# HF1R00.net
KiCad netlist of a schematic drawn in EAGLE
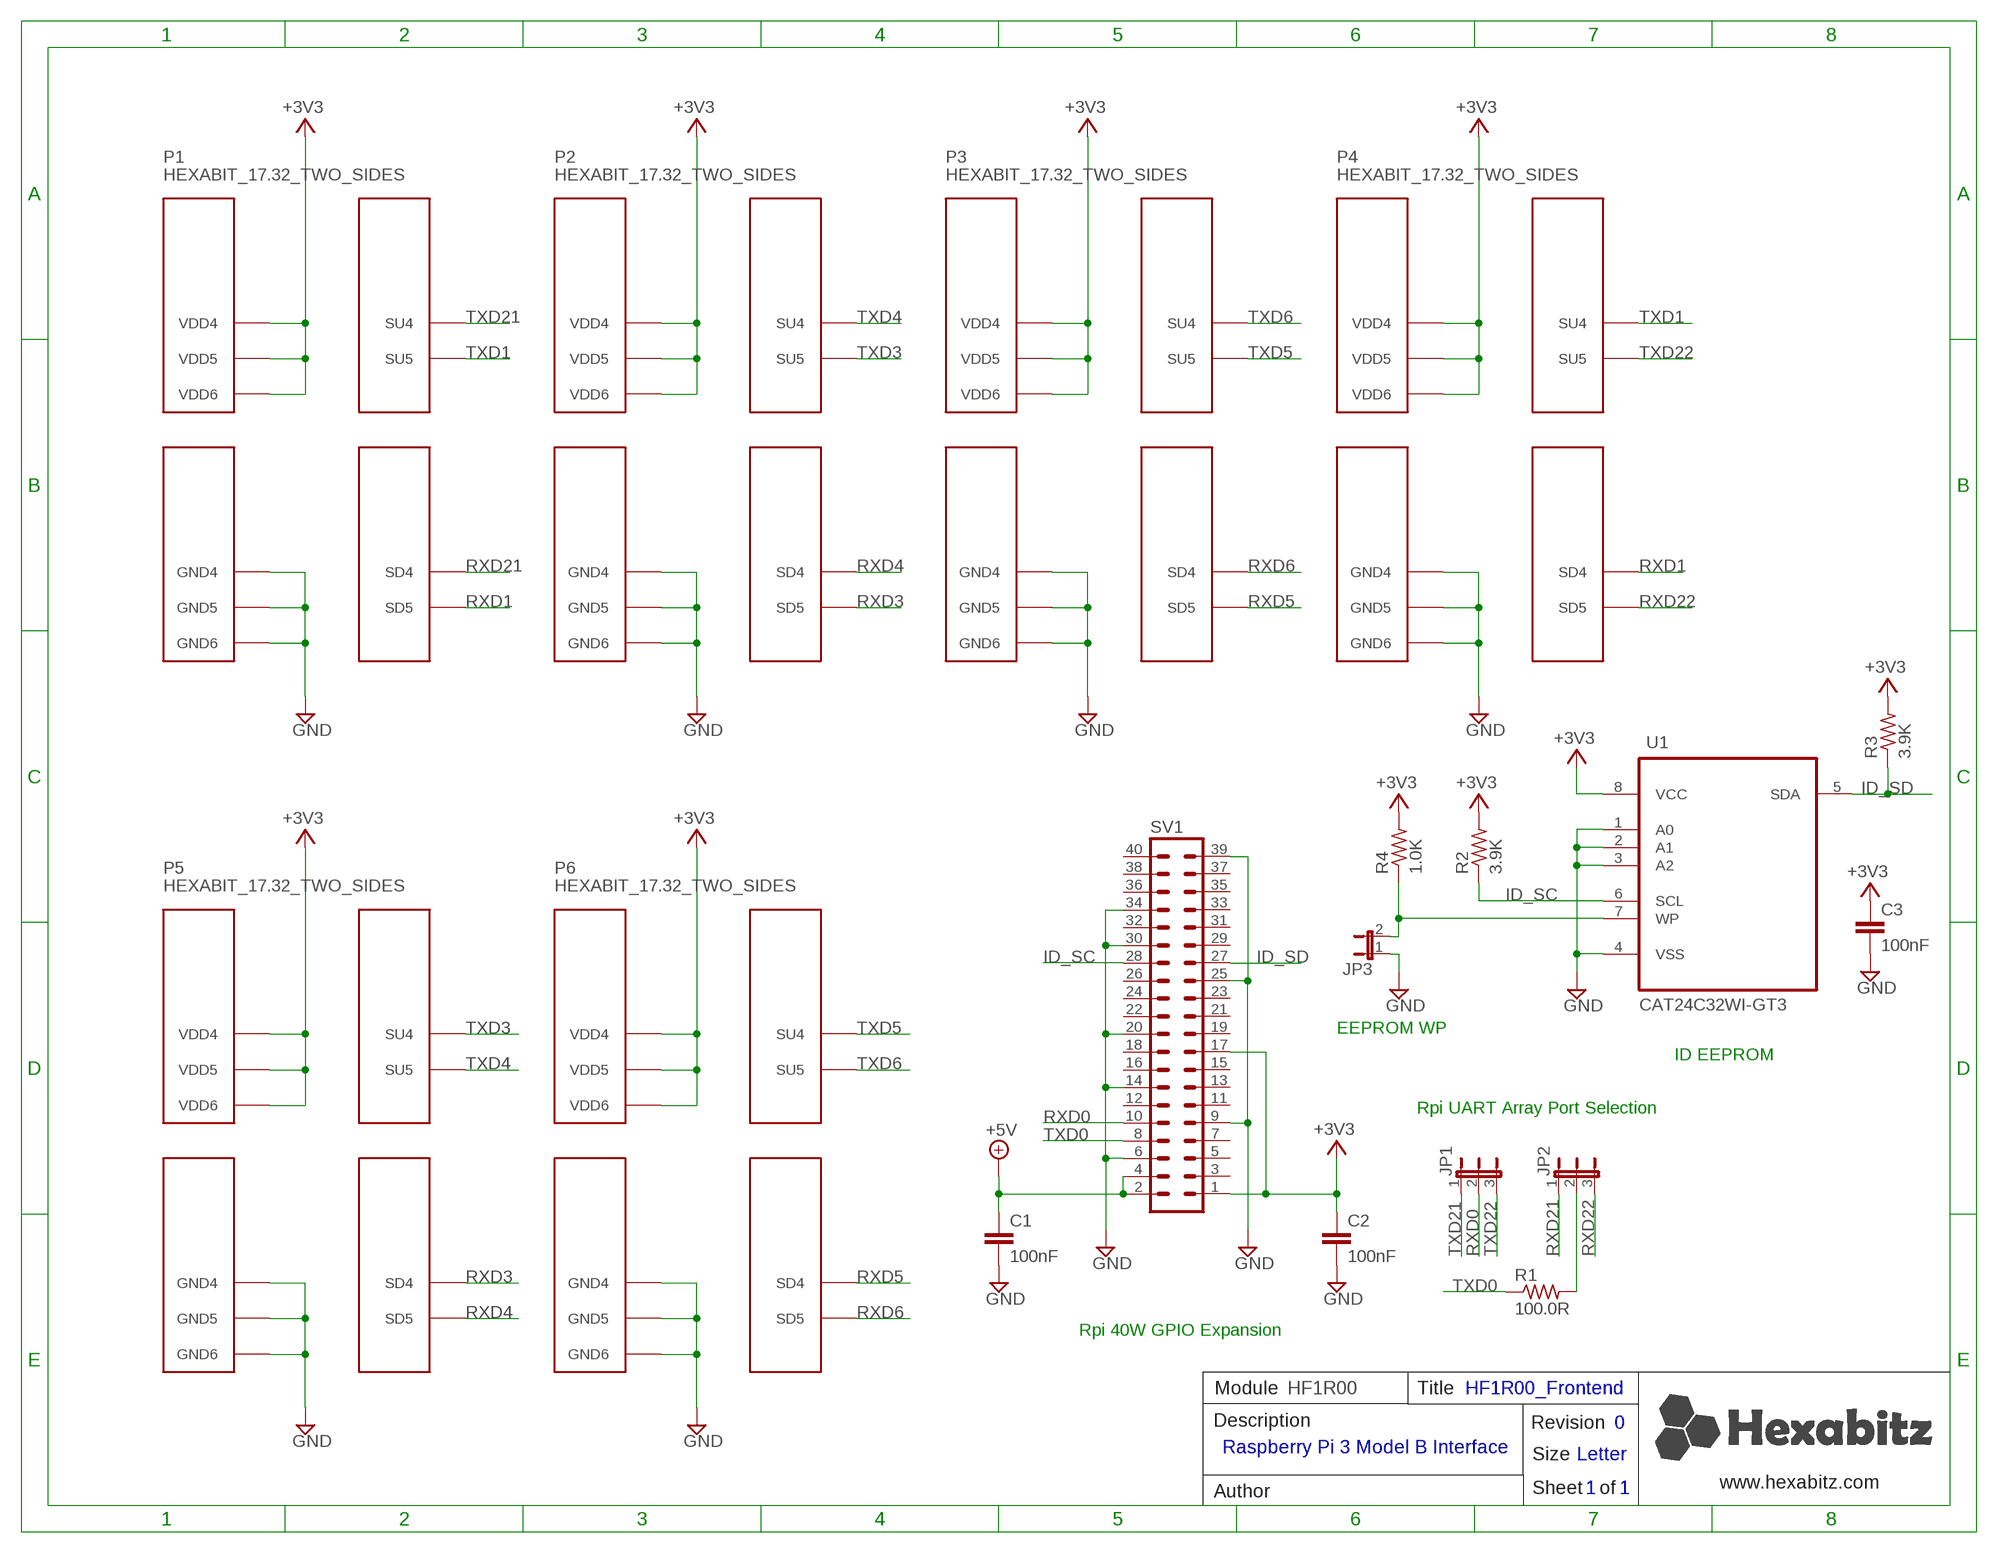
[diagram p0: schematic, sheet 1]

(export (version "E")
  (design (tool "Eeschema 10.0.6"))
  (components
    (comp (ref "C1")
      (value "100nF")
      (footprint "eagle-import:C-0603")
      (fields
        (field (name "CAPACITANCE") "100nF")
        (field (name "MFN") "KEMET")
        (field (name "MPN") "C0603C104K8RACTU")
        (field (name "OCTOPART_URL") "https://octopart.com/c0603c104k8ractu-kemet-145075?r=sp&s=9bS9ASSwSEqMCE9KBEQZ0g")
        (field (name "TOLERANCE") "10V")
        (field (name "VOLTAGE_RATING") "10%")
      )
      (libsource (lib "eagle-import") (part "C-0603"))
    )
    (comp (ref "C2")
      (value "100nF")
      (footprint "eagle-import:C-0603")
      (fields
        (field (name "CAPACITANCE") "100nF")
        (field (name "MFN") "KEMET")
        (field (name "MPN") "C0603C104K8RACTU")
        (field (name "OCTOPART_URL") "https://octopart.com/c0603c104k8ractu-kemet-145075?r=sp&s=9bS9ASSwSEqMCE9KBEQZ0g")
        (field (name "TOLERANCE") "10V")
        (field (name "VOLTAGE_RATING") "10%")
      )
      (libsource (lib "eagle-import") (part "C-0603"))
    )
    (comp (ref "C3")
      (value "100nF")
      (footprint "eagle-import:C-0603")
      (fields
        (field (name "CAPACITANCE") "100nF")
        (field (name "MFN") "KEMET")
        (field (name "MPN") "C0603C104K8RACTU")
        (field (name "OCTOPART_URL") "https://octopart.com/c0603c104k8ractu-kemet-145075?r=sp&s=9bS9ASSwSEqMCE9KBEQZ0g")
        (field (name "TOLERANCE") "10V")
        (field (name "VOLTAGE_RATING") "10%")
      )
      (libsource (lib "eagle-import") (part "C-0603"))
    )
    (comp (ref "JP1")
      (value "61300311121")
      (footprint "eagle-import:JP2")
      (libsource (lib "eagle-import") (part "JP2E"))
    )
    (comp (ref "JP2")
      (value "61300311121")
      (footprint "eagle-import:JP2")
      (libsource (lib "eagle-import") (part "JP2E"))
    )
    (comp (ref "JP3")
      (value "61300211121")
      (footprint "eagle-import:JP1")
      (libsource (lib "eagle-import") (part "JP1E"))
    )
    (comp (ref "P1")
      (value "HEXABIT_17.32_TWO_SIDES")
      (footprint "eagle-import:HEXABIT_17.32_TWO_SIDES")
      (libsource (lib "eagle-import") (part "HEXABIT_?_TWO_SIDES17.32"))
    )
    (comp (ref "P2")
      (value "HEXABIT_17.32_TWO_SIDES")
      (footprint "eagle-import:HEXABIT_17.32_TWO_SIDES")
      (libsource (lib "eagle-import") (part "HEXABIT_?_TWO_SIDES17.32"))
    )
    (comp (ref "P3")
      (value "HEXABIT_17.32_TWO_SIDES")
      (footprint "eagle-import:HEXABIT_17.32_TWO_SIDES")
      (libsource (lib "eagle-import") (part "HEXABIT_?_TWO_SIDES17.32"))
    )
    (comp (ref "P4")
      (value "HEXABIT_17.32_TWO_SIDES")
      (footprint "eagle-import:HEXABIT_17.32_TWO_SIDES")
      (libsource (lib "eagle-import") (part "HEXABIT_?_TWO_SIDES17.32"))
    )
    (comp (ref "P5")
      (value "HEXABIT_17.32_TWO_SIDES")
      (footprint "eagle-import:HEXABIT_17.32_TWO_SIDES")
      (libsource (lib "eagle-import") (part "HEXABIT_?_TWO_SIDES17.32"))
    )
    (comp (ref "P6")
      (value "HEXABIT_17.32_TWO_SIDES")
      (footprint "eagle-import:HEXABIT_17.32_TWO_SIDES")
      (libsource (lib "eagle-import") (part "HEXABIT_?_TWO_SIDES17.32"))
    )
    (comp (ref "R1")
      (value "100.0R")
      (footprint "eagle-import:R-0603")
      (fields
        (field (name "MFN") "Panasonic ")
        (field (name "MPN") "ERJ-PA3F1000V")
        (field (name "OCTOPART_URL") "https://octopart.com/erj-pa3f1000v-panasonic-51302178?r=sp&s=FtfQlVmZQ6G_o34px3VECw")
        (field (name "RESISTANCE") "100.0 Ohm")
        (field (name "TOLERANCE") "1%")
      )
      (libsource (lib "eagle-import") (part "R-0603"))
    )
    (comp (ref "R2")
      (value "3.9K")
      (footprint "eagle-import:R-0603")
      (fields
        (field (name "MFN") "Vishay")
        (field (name "MPN") "CRCW06033K90FKEA")
        (field (name "OCTOPART_URL") "https://octopart.com/crcw06033k90fkea-vishay-40019003?r=sp&s=g-tYgB-WSDSQxdPWmNeinA")
        (field (name "RESISTANCE") "3.9 kOhm")
        (field (name "TOLERANCE") "1%")
      )
      (libsource (lib "eagle-import") (part "R-0603"))
    )
    (comp (ref "R3")
      (value "3.9K")
      (footprint "eagle-import:R-0603")
      (fields
        (field (name "MFN") "Vishay")
        (field (name "MPN") "CRCW06033K90FKEA")
        (field (name "OCTOPART_URL") "https://octopart.com/crcw06033k90fkea-vishay-40019003?r=sp&s=g-tYgB-WSDSQxdPWmNeinA")
        (field (name "RESISTANCE") "3.9 kOhm")
        (field (name "TOLERANCE") "1%")
      )
      (libsource (lib "eagle-import") (part "R-0603"))
    )
    (comp (ref "R4")
      (value "1.0K")
      (footprint "eagle-import:R-0603")
      (fields
        (field (name "MFN") "Panasonic")
        (field (name "MPN") "ERJ-3EKF1001V")
        (field (name "OCTOPART_URL") "https://octopart.com/erj-3ekf1001v-panasonic-55403646?r=sp&s=_UtQAJDmTsiNho0Uqf11iA")
        (field (name "RESISTANCE") "1.0 kOhm")
        (field (name "TOLERANCE") "1%")
      )
      (libsource (lib "eagle-import") (part "R-0603"))
    )
    (comp (ref "SV1")
      (value "PPTC202LFBN-RC")
      (footprint "eagle-import:MA20-2")
      (fields (field (name "MF") " Sullins Connector Solutions") (field (name "MPN") "PPTC202LFBN-RC"))
      (libsource (lib "eagle-import") (part "MA20-2"))
    )
    (comp (ref "U1")
      (value "CAT24C32WI-GT3")
      (footprint "eagle-import:SOIC127P600X175-8N")
      (libsource (lib "eagle-import") (part "CAT24C32WI-GT3"))
    )
  )
  (nets
    (net (code "1") (name "+3V3") (class "Default")
      (node (ref "C2") (pin "1") (pinfunction "1_1") (pintype "passive"))
      (node (ref "C3") (pin "1") (pinfunction "1_1") (pintype "passive"))
      (node (ref "P1") (pin "PAD_PU10") (pinfunction "VDD4_PAD_PU10") (pintype "power_in"))
      (node (ref "P1") (pin "PAD_PU11") (pinfunction "VDD5_PAD_PU11") (pintype "power_in"))
      (node (ref "P1") (pin "PAD_PU12") (pinfunction "VDD6_PAD_PU12") (pintype "power_in"))
      (node (ref "P2") (pin "PAD_PU10") (pinfunction "VDD4_PAD_PU10") (pintype "power_in"))
      (node (ref "P2") (pin "PAD_PU11") (pinfunction "VDD5_PAD_PU11") (pintype "power_in"))
      (node (ref "P2") (pin "PAD_PU12") (pinfunction "VDD6_PAD_PU12") (pintype "power_in"))
      (node (ref "P3") (pin "PAD_PU10") (pinfunction "VDD4_PAD_PU10") (pintype "power_in"))
      (node (ref "P3") (pin "PAD_PU11") (pinfunction "VDD5_PAD_PU11") (pintype "power_in"))
      (node (ref "P3") (pin "PAD_PU12") (pinfunction "VDD6_PAD_PU12") (pintype "power_in"))
      (node (ref "P4") (pin "PAD_PU10") (pinfunction "VDD4_PAD_PU10") (pintype "power_in"))
      (node (ref "P4") (pin "PAD_PU11") (pinfunction "VDD5_PAD_PU11") (pintype "power_in"))
      (node (ref "P4") (pin "PAD_PU12") (pinfunction "VDD6_PAD_PU12") (pintype "power_in"))
      (node (ref "P5") (pin "PAD_PU10") (pinfunction "VDD4_PAD_PU10") (pintype "power_in"))
      (node (ref "P5") (pin "PAD_PU11") (pinfunction "VDD5_PAD_PU11") (pintype "power_in"))
      (node (ref "P5") (pin "PAD_PU12") (pinfunction "VDD6_PAD_PU12") (pintype "power_in"))
      (node (ref "P6") (pin "PAD_PU10") (pinfunction "VDD4_PAD_PU10") (pintype "power_in"))
      (node (ref "P6") (pin "PAD_PU11") (pinfunction "VDD5_PAD_PU11") (pintype "power_in"))
      (node (ref "P6") (pin "PAD_PU12") (pinfunction "VDD6_PAD_PU12") (pintype "power_in"))
      (node (ref "R2") (pin "2") (pinfunction "2_2") (pintype "passive"))
      (node (ref "R3") (pin "2") (pinfunction "2_2") (pintype "passive"))
      (node (ref "R4") (pin "2") (pinfunction "2_2") (pintype "passive"))
      (node (ref "SV1") (pin "1") (pinfunction "1_1") (pintype "passive"))
      (node (ref "SV1") (pin "17") (pinfunction "17_17") (pintype "passive"))
      (node (ref "U1") (pin "8") (pinfunction "VCC_8") (pintype "power_in"))
    )
    (net (code "2") (name "+5V") (class "Default")
      (node (ref "C1") (pin "1") (pinfunction "1_1") (pintype "passive"))
      (node (ref "SV1") (pin "2") (pinfunction "2_2") (pintype "passive"))
      (node (ref "SV1") (pin "4") (pinfunction "4_4") (pintype "passive"))
    )
    (net (code "3") (name "/ID_SC") (class "Default")
      (node (ref "R2") (pin "1") (pinfunction "1_1") (pintype "passive"))
      (node (ref "SV1") (pin "28") (pinfunction "28_28") (pintype "passive"))
      (node (ref "U1") (pin "6") (pinfunction "SCL_6") (pintype "input"))
    )
    (net (code "4") (name "/ID_SD") (class "Default")
      (node (ref "R3") (pin "1") (pinfunction "1_1") (pintype "passive"))
      (node (ref "SV1") (pin "27") (pinfunction "27_27") (pintype "passive"))
      (node (ref "U1") (pin "5") (pinfunction "SDA_5") (pintype "bidirectional"))
    )
    (net (code "5") (name "/RXD0") (class "Default")
      (node (ref "JP1") (pin "2") (pinfunction "2_2") (pintype "passive"))
      (node (ref "SV1") (pin "10") (pinfunction "10_10") (pintype "passive"))
    )
    (net (code "6") (name "/RXD1") (class "Default")
      (node (ref "P1") (pin "PAD_PD5") (pinfunction "SD5_PAD_PD5") (pintype "bidirectional"))
      (node (ref "P4") (pin "PAD_PD4") (pinfunction "SD4_PAD_PD4") (pintype "bidirectional"))
    )
    (net (code "7") (name "/RXD3") (class "Default")
      (node (ref "P2") (pin "PAD_PD5") (pinfunction "SD5_PAD_PD5") (pintype "bidirectional"))
      (node (ref "P5") (pin "PAD_PD4") (pinfunction "SD4_PAD_PD4") (pintype "bidirectional"))
    )
    (net (code "8") (name "/RXD4") (class "Default")
      (node (ref "P2") (pin "PAD_PD4") (pinfunction "SD4_PAD_PD4") (pintype "bidirectional"))
      (node (ref "P5") (pin "PAD_PD5") (pinfunction "SD5_PAD_PD5") (pintype "bidirectional"))
    )
    (net (code "9") (name "/RXD5") (class "Default")
      (node (ref "P3") (pin "PAD_PD5") (pinfunction "SD5_PAD_PD5") (pintype "bidirectional"))
      (node (ref "P6") (pin "PAD_PD4") (pinfunction "SD4_PAD_PD4") (pintype "bidirectional"))
    )
    (net (code "10") (name "/RXD6") (class "Default")
      (node (ref "P3") (pin "PAD_PD4") (pinfunction "SD4_PAD_PD4") (pintype "bidirectional"))
      (node (ref "P6") (pin "PAD_PD5") (pinfunction "SD5_PAD_PD5") (pintype "bidirectional"))
    )
    (net (code "11") (name "/RXD21") (class "Default")
      (node (ref "JP2") (pin "1") (pinfunction "1_1") (pintype "passive"))
      (node (ref "P1") (pin "PAD_PD4") (pinfunction "SD4_PAD_PD4") (pintype "bidirectional"))
    )
    (net (code "12") (name "/RXD22") (class "Default")
      (node (ref "JP2") (pin "3") (pinfunction "3_3") (pintype "passive"))
      (node (ref "P4") (pin "PAD_PD5") (pinfunction "SD5_PAD_PD5") (pintype "bidirectional"))
    )
    (net (code "13") (name "/TXD0") (class "Default")
      (node (ref "R1") (pin "1") (pinfunction "1_1") (pintype "passive"))
      (node (ref "SV1") (pin "8") (pinfunction "8_8") (pintype "passive"))
    )
    (net (code "14") (name "/TXD1") (class "Default")
      (node (ref "P1") (pin "PAD_PU5") (pinfunction "SU5_PAD_PU5") (pintype "bidirectional"))
      (node (ref "P4") (pin "PAD_PU4") (pinfunction "SU4_PAD_PU4") (pintype "bidirectional"))
    )
    (net (code "15") (name "/TXD3") (class "Default")
      (node (ref "P2") (pin "PAD_PU5") (pinfunction "SU5_PAD_PU5") (pintype "bidirectional"))
      (node (ref "P5") (pin "PAD_PU4") (pinfunction "SU4_PAD_PU4") (pintype "bidirectional"))
    )
    (net (code "16") (name "/TXD4") (class "Default")
      (node (ref "P2") (pin "PAD_PU4") (pinfunction "SU4_PAD_PU4") (pintype "bidirectional"))
      (node (ref "P5") (pin "PAD_PU5") (pinfunction "SU5_PAD_PU5") (pintype "bidirectional"))
    )
    (net (code "17") (name "/TXD5") (class "Default")
      (node (ref "P3") (pin "PAD_PU5") (pinfunction "SU5_PAD_PU5") (pintype "bidirectional"))
      (node (ref "P6") (pin "PAD_PU4") (pinfunction "SU4_PAD_PU4") (pintype "bidirectional"))
    )
    (net (code "18") (name "/TXD6") (class "Default")
      (node (ref "P3") (pin "PAD_PU4") (pinfunction "SU4_PAD_PU4") (pintype "bidirectional"))
      (node (ref "P6") (pin "PAD_PU5") (pinfunction "SU5_PAD_PU5") (pintype "bidirectional"))
    )
    (net (code "19") (name "/TXD21") (class "Default")
      (node (ref "JP1") (pin "1") (pinfunction "1_1") (pintype "passive"))
      (node (ref "P1") (pin "PAD_PU4") (pinfunction "SU4_PAD_PU4") (pintype "bidirectional"))
    )
    (net (code "20") (name "/TXD22") (class "Default")
      (node (ref "JP1") (pin "3") (pinfunction "3_3") (pintype "passive"))
      (node (ref "P4") (pin "PAD_PU5") (pinfunction "SU5_PAD_PU5") (pintype "bidirectional"))
    )
    (net (code "21") (name "GND") (class "Default")
      (node (ref "C1") (pin "2") (pinfunction "2_2") (pintype "passive"))
      (node (ref "C2") (pin "2") (pinfunction "2_2") (pintype "passive"))
      (node (ref "C3") (pin "2") (pinfunction "2_2") (pintype "passive"))
      (node (ref "JP3") (pin "1") (pinfunction "1_1") (pintype "passive"))
      (node (ref "P1") (pin "PAD_PD10") (pinfunction "GND4_PAD_PD10") (pintype "power_in"))
      (node (ref "P1") (pin "PAD_PD11") (pinfunction "GND5_PAD_PD11") (pintype "power_in"))
      (node (ref "P1") (pin "PAD_PD12") (pinfunction "GND6_PAD_PD12") (pintype "power_in"))
      (node (ref "P2") (pin "PAD_PD10") (pinfunction "GND4_PAD_PD10") (pintype "power_in"))
      (node (ref "P2") (pin "PAD_PD11") (pinfunction "GND5_PAD_PD11") (pintype "power_in"))
      (node (ref "P2") (pin "PAD_PD12") (pinfunction "GND6_PAD_PD12") (pintype "power_in"))
      (node (ref "P3") (pin "PAD_PD10") (pinfunction "GND4_PAD_PD10") (pintype "power_in"))
      (node (ref "P3") (pin "PAD_PD11") (pinfunction "GND5_PAD_PD11") (pintype "power_in"))
      (node (ref "P3") (pin "PAD_PD12") (pinfunction "GND6_PAD_PD12") (pintype "power_in"))
      (node (ref "P4") (pin "PAD_PD10") (pinfunction "GND4_PAD_PD10") (pintype "power_in"))
      (node (ref "P4") (pin "PAD_PD11") (pinfunction "GND5_PAD_PD11") (pintype "power_in"))
      (node (ref "P4") (pin "PAD_PD12") (pinfunction "GND6_PAD_PD12") (pintype "power_in"))
      (node (ref "P5") (pin "PAD_PD10") (pinfunction "GND4_PAD_PD10") (pintype "power_in"))
      (node (ref "P5") (pin "PAD_PD11") (pinfunction "GND5_PAD_PD11") (pintype "power_in"))
      (node (ref "P5") (pin "PAD_PD12") (pinfunction "GND6_PAD_PD12") (pintype "power_in"))
      (node (ref "P6") (pin "PAD_PD10") (pinfunction "GND4_PAD_PD10") (pintype "power_in"))
      (node (ref "P6") (pin "PAD_PD11") (pinfunction "GND5_PAD_PD11") (pintype "power_in"))
      (node (ref "P6") (pin "PAD_PD12") (pinfunction "GND6_PAD_PD12") (pintype "power_in"))
      (node (ref "SV1") (pin "14") (pinfunction "14_14") (pintype "passive"))
      (node (ref "SV1") (pin "20") (pinfunction "20_20") (pintype "passive"))
      (node (ref "SV1") (pin "25") (pinfunction "25_25") (pintype "passive"))
      (node (ref "SV1") (pin "30") (pinfunction "30_30") (pintype "passive"))
      (node (ref "SV1") (pin "34") (pinfunction "34_34") (pintype "passive"))
      (node (ref "SV1") (pin "39") (pinfunction "39_39") (pintype "passive"))
      (node (ref "SV1") (pin "6") (pinfunction "6_6") (pintype "passive"))
      (node (ref "SV1") (pin "9") (pinfunction "9_9") (pintype "passive"))
      (node (ref "U1") (pin "1") (pinfunction "A0_1") (pintype "input"))
      (node (ref "U1") (pin "2") (pinfunction "A1_2") (pintype "input"))
      (node (ref "U1") (pin "3") (pinfunction "A2_3") (pintype "input"))
      (node (ref "U1") (pin "4") (pinfunction "VSS_4") (pintype "passive"))
    )
    (net (code "22") (name "Net-(JP2-Pad2)") (class "Default")
      (node (ref "JP2") (pin "2") (pinfunction "2_2") (pintype "passive"))
      (node (ref "R1") (pin "2") (pinfunction "2_2") (pintype "passive"))
    )
    (net (code "23") (name "Net-(U1-WP)") (class "Default")
      (node (ref "JP3") (pin "2") (pinfunction "2_2") (pintype "passive"))
      (node (ref "R4") (pin "1") (pinfunction "1_1") (pintype "passive"))
      (node (ref "U1") (pin "7") (pinfunction "WP_7") (pintype "input"))
    )
    (net (code "24") (name "unconnected-(SV1-Pad3)") (class "Default")
      (node (ref "SV1") (pin "3") (pinfunction "3_3") (pintype "passive"))
    )
    (net (code "25") (name "unconnected-(SV1-Pad5)") (class "Default")
      (node (ref "SV1") (pin "5") (pinfunction "5_5") (pintype "passive"))
    )
    (net (code "26") (name "unconnected-(SV1-Pad7)") (class "Default")
      (node (ref "SV1") (pin "7") (pinfunction "7_7") (pintype "passive"))
    )
    (net (code "27") (name "unconnected-(SV1-Pad11)") (class "Default")
      (node (ref "SV1") (pin "11") (pinfunction "11_11") (pintype "passive"))
    )
    (net (code "28") (name "unconnected-(SV1-Pad12)") (class "Default")
      (node (ref "SV1") (pin "12") (pinfunction "12_12") (pintype "passive"))
    )
    (net (code "29") (name "unconnected-(SV1-Pad13)") (class "Default")
      (node (ref "SV1") (pin "13") (pinfunction "13_13") (pintype "passive"))
    )
    (net (code "30") (name "unconnected-(SV1-Pad15)") (class "Default")
      (node (ref "SV1") (pin "15") (pinfunction "15_15") (pintype "passive"))
    )
    (net (code "31") (name "unconnected-(SV1-Pad16)") (class "Default")
      (node (ref "SV1") (pin "16") (pinfunction "16_16") (pintype "passive"))
    )
    (net (code "32") (name "unconnected-(SV1-Pad18)") (class "Default")
      (node (ref "SV1") (pin "18") (pinfunction "18_18") (pintype "passive"))
    )
    (net (code "33") (name "unconnected-(SV1-Pad19)") (class "Default")
      (node (ref "SV1") (pin "19") (pinfunction "19_19") (pintype "passive"))
    )
    (net (code "34") (name "unconnected-(SV1-Pad21)") (class "Default")
      (node (ref "SV1") (pin "21") (pinfunction "21_21") (pintype "passive"))
    )
    (net (code "35") (name "unconnected-(SV1-Pad22)") (class "Default")
      (node (ref "SV1") (pin "22") (pinfunction "22_22") (pintype "passive"))
    )
    (net (code "36") (name "unconnected-(SV1-Pad23)") (class "Default")
      (node (ref "SV1") (pin "23") (pinfunction "23_23") (pintype "passive"))
    )
    (net (code "37") (name "unconnected-(SV1-Pad24)") (class "Default")
      (node (ref "SV1") (pin "24") (pinfunction "24_24") (pintype "passive"))
    )
    (net (code "38") (name "unconnected-(SV1-Pad26)") (class "Default")
      (node (ref "SV1") (pin "26") (pinfunction "26_26") (pintype "passive"))
    )
    (net (code "39") (name "unconnected-(SV1-Pad29)") (class "Default")
      (node (ref "SV1") (pin "29") (pinfunction "29_29") (pintype "passive"))
    )
    (net (code "40") (name "unconnected-(SV1-Pad31)") (class "Default")
      (node (ref "SV1") (pin "31") (pinfunction "31_31") (pintype "passive"))
    )
    (net (code "41") (name "unconnected-(SV1-Pad32)") (class "Default")
      (node (ref "SV1") (pin "32") (pinfunction "32_32") (pintype "passive"))
    )
    (net (code "42") (name "unconnected-(SV1-Pad33)") (class "Default")
      (node (ref "SV1") (pin "33") (pinfunction "33_33") (pintype "passive"))
    )
    (net (code "43") (name "unconnected-(SV1-Pad35)") (class "Default")
      (node (ref "SV1") (pin "35") (pinfunction "35_35") (pintype "passive"))
    )
    (net (code "44") (name "unconnected-(SV1-Pad36)") (class "Default")
      (node (ref "SV1") (pin "36") (pinfunction "36_36") (pintype "passive"))
    )
    (net (code "45") (name "unconnected-(SV1-Pad37)") (class "Default")
      (node (ref "SV1") (pin "37") (pinfunction "37_37") (pintype "passive"))
    )
    (net (code "46") (name "unconnected-(SV1-Pad38)") (class "Default")
      (node (ref "SV1") (pin "38") (pinfunction "38_38") (pintype "passive"))
    )
    (net (code "47") (name "unconnected-(SV1-Pad40)") (class "Default")
      (node (ref "SV1") (pin "40") (pinfunction "40_40") (pintype "passive"))
    )
  )
)
